# Left_Eye_Module.net
KiCad netlist of a schematic drawn in Altium Designer
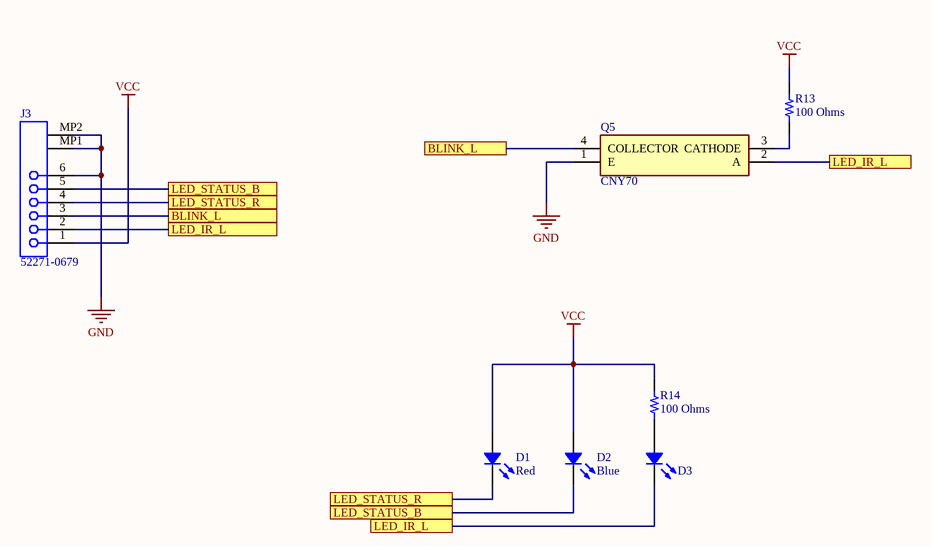
[diagram p0: Left Eye Module.SchDoc]

(export (version "E")
  (design (tool "Eeschema 10.0.6"))
  (components
    (comp (ref "D1")
      (value "Red")
      (footprint "LED 1206_3216 RED")
      (description "LED RED DIFFUSED 1206 SMD")
      (fields
        (field (name "PART NUMBER") "SML-LX1206IW-TR")
        (field (name "MANUFACTURER") "Lumex Opto/Components Inc.")
      )
      (libsource (lib "Celestial Altium Library - altium_library") (part "LED"))
    )
    (comp (ref "D2")
      (value "Blue")
      (footprint "LED 1206_3216 BLUE")
      (description "LED BLUE CLEAR 1206 SMD")
      (fields (field (name "PART NUMBER") "IN-S126ATB") (field (name "MANUFACTURER") "Inolux"))
      (libsource (lib "Celestial Altium Library - altium_library") (part "LED"))
    )
    (comp (ref "D3")
      (value "~")
      (footprint "OP269A")
      (description "Chip LED")
      (libsource (lib "Voidstar Semi") (part "LED"))
    )
    (comp (ref "J3")
      (value "52271-0679")
      (footprint "MOLX-52271-0679")
      (fields (field (name "MANUFACTURER") "Molex"))
      (libsource (lib "Molex FFC - FPC Connectors (SMT)") (part "52271-0679"))
    )
    (comp (ref "Q5")
      (value "CNY70")
      (footprint "SamacSys:CNY70")
      (description "Transistor")
      (fields (field (name "MOUSER2 PART NUMBER") "782-CNY70"))
      (libsource (lib "SamacSys") (part "CNY70"))
    )
    (comp (ref "R13")
      (value "100 Ohms")
      (footprint "RES 0603_1608")
      (description "RES 100 OHM 1% 1/10W 0603")
      (fields
        (field (name "PART NUMBER") "RMCF0603FG100R")
        (field (name "MANUFACTURER") "Stackpole Electronics Inc")
      )
      (libsource (lib "Celestial Altium Library - altium_library") (part "Resistor"))
    )
    (comp (ref "R14")
      (value "100 Ohms")
      (footprint "RES 0603_1608")
      (description "RES 100 OHM 1% 1/10W 0603")
      (fields
        (field (name "PART NUMBER") "RMCF0603FG100R")
        (field (name "MANUFACTURER") "Stackpole Electronics Inc")
      )
      (libsource (lib "Celestial Altium Library - altium_library") (part "Resistor"))
    )
  )
  (nets
    (net (code "1") (name "/BLINK_L") (class "Default")
      (node (ref "J3") (pin "3") (pinfunction "3_3") (pintype "passive"))
      (node (ref "Q5") (pin "4") (pinfunction "COLLECTOR_4") (pintype "passive"))
    )
    (net (code "2") (name "/LED_IR_L") (class "Default")
      (node (ref "D3") (pin "2") (pinfunction "2_2") (pintype "passive"))
      (node (ref "J3") (pin "2") (pinfunction "2_2") (pintype "passive"))
      (node (ref "Q5") (pin "2") (pinfunction "A_2") (pintype "passive"))
    )
    (net (code "3") (name "/LED_STATUS_B") (class "Default")
      (node (ref "D2") (pin "2") (pinfunction "2_2") (pintype "passive"))
      (node (ref "J3") (pin "5") (pinfunction "5_5") (pintype "passive"))
    )
    (net (code "4") (name "/LED_STATUS_R") (class "Default")
      (node (ref "D1") (pin "2") (pinfunction "2_2") (pintype "passive"))
      (node (ref "J3") (pin "4") (pinfunction "4_4") (pintype "passive"))
    )
    (net (code "5") (name "GND") (class "Default")
      (node (ref "J3") (pin "6") (pinfunction "6_6") (pintype "passive"))
      (node (ref "J3") (pin "MP1") (pinfunction "MP1_MP1") (pintype "passive"))
      (node (ref "J3") (pin "MP2") (pinfunction "MP2_MP2") (pintype "passive"))
      (node (ref "Q5") (pin "1") (pinfunction "E_1") (pintype "passive"))
    )
    (net (code "6") (name "Net-(D3-Pad1)") (class "Default")
      (node (ref "D3") (pin "1") (pinfunction "1_1") (pintype "passive"))
      (node (ref "R14") (pin "1") (pinfunction "1_1") (pintype "passive"))
    )
    (net (code "7") (name "Net-(Q5-CATHODE)") (class "Default")
      (node (ref "Q5") (pin "3") (pinfunction "CATHODE_3") (pintype "passive"))
      (node (ref "R13") (pin "1") (pinfunction "1_1") (pintype "passive"))
    )
    (net (code "8") (name "VCC") (class "Default")
      (node (ref "D1") (pin "1") (pinfunction "1_1") (pintype "passive"))
      (node (ref "D2") (pin "1") (pinfunction "1_1") (pintype "passive"))
      (node (ref "J3") (pin "1") (pinfunction "1_1") (pintype "passive"))
      (node (ref "R13") (pin "2") (pinfunction "2_2") (pintype "passive"))
      (node (ref "R14") (pin "2") (pinfunction "2_2") (pintype "passive"))
    )
  )
)
